# Charging.net
KiCad netlist of a schematic drawn in Altium Designer
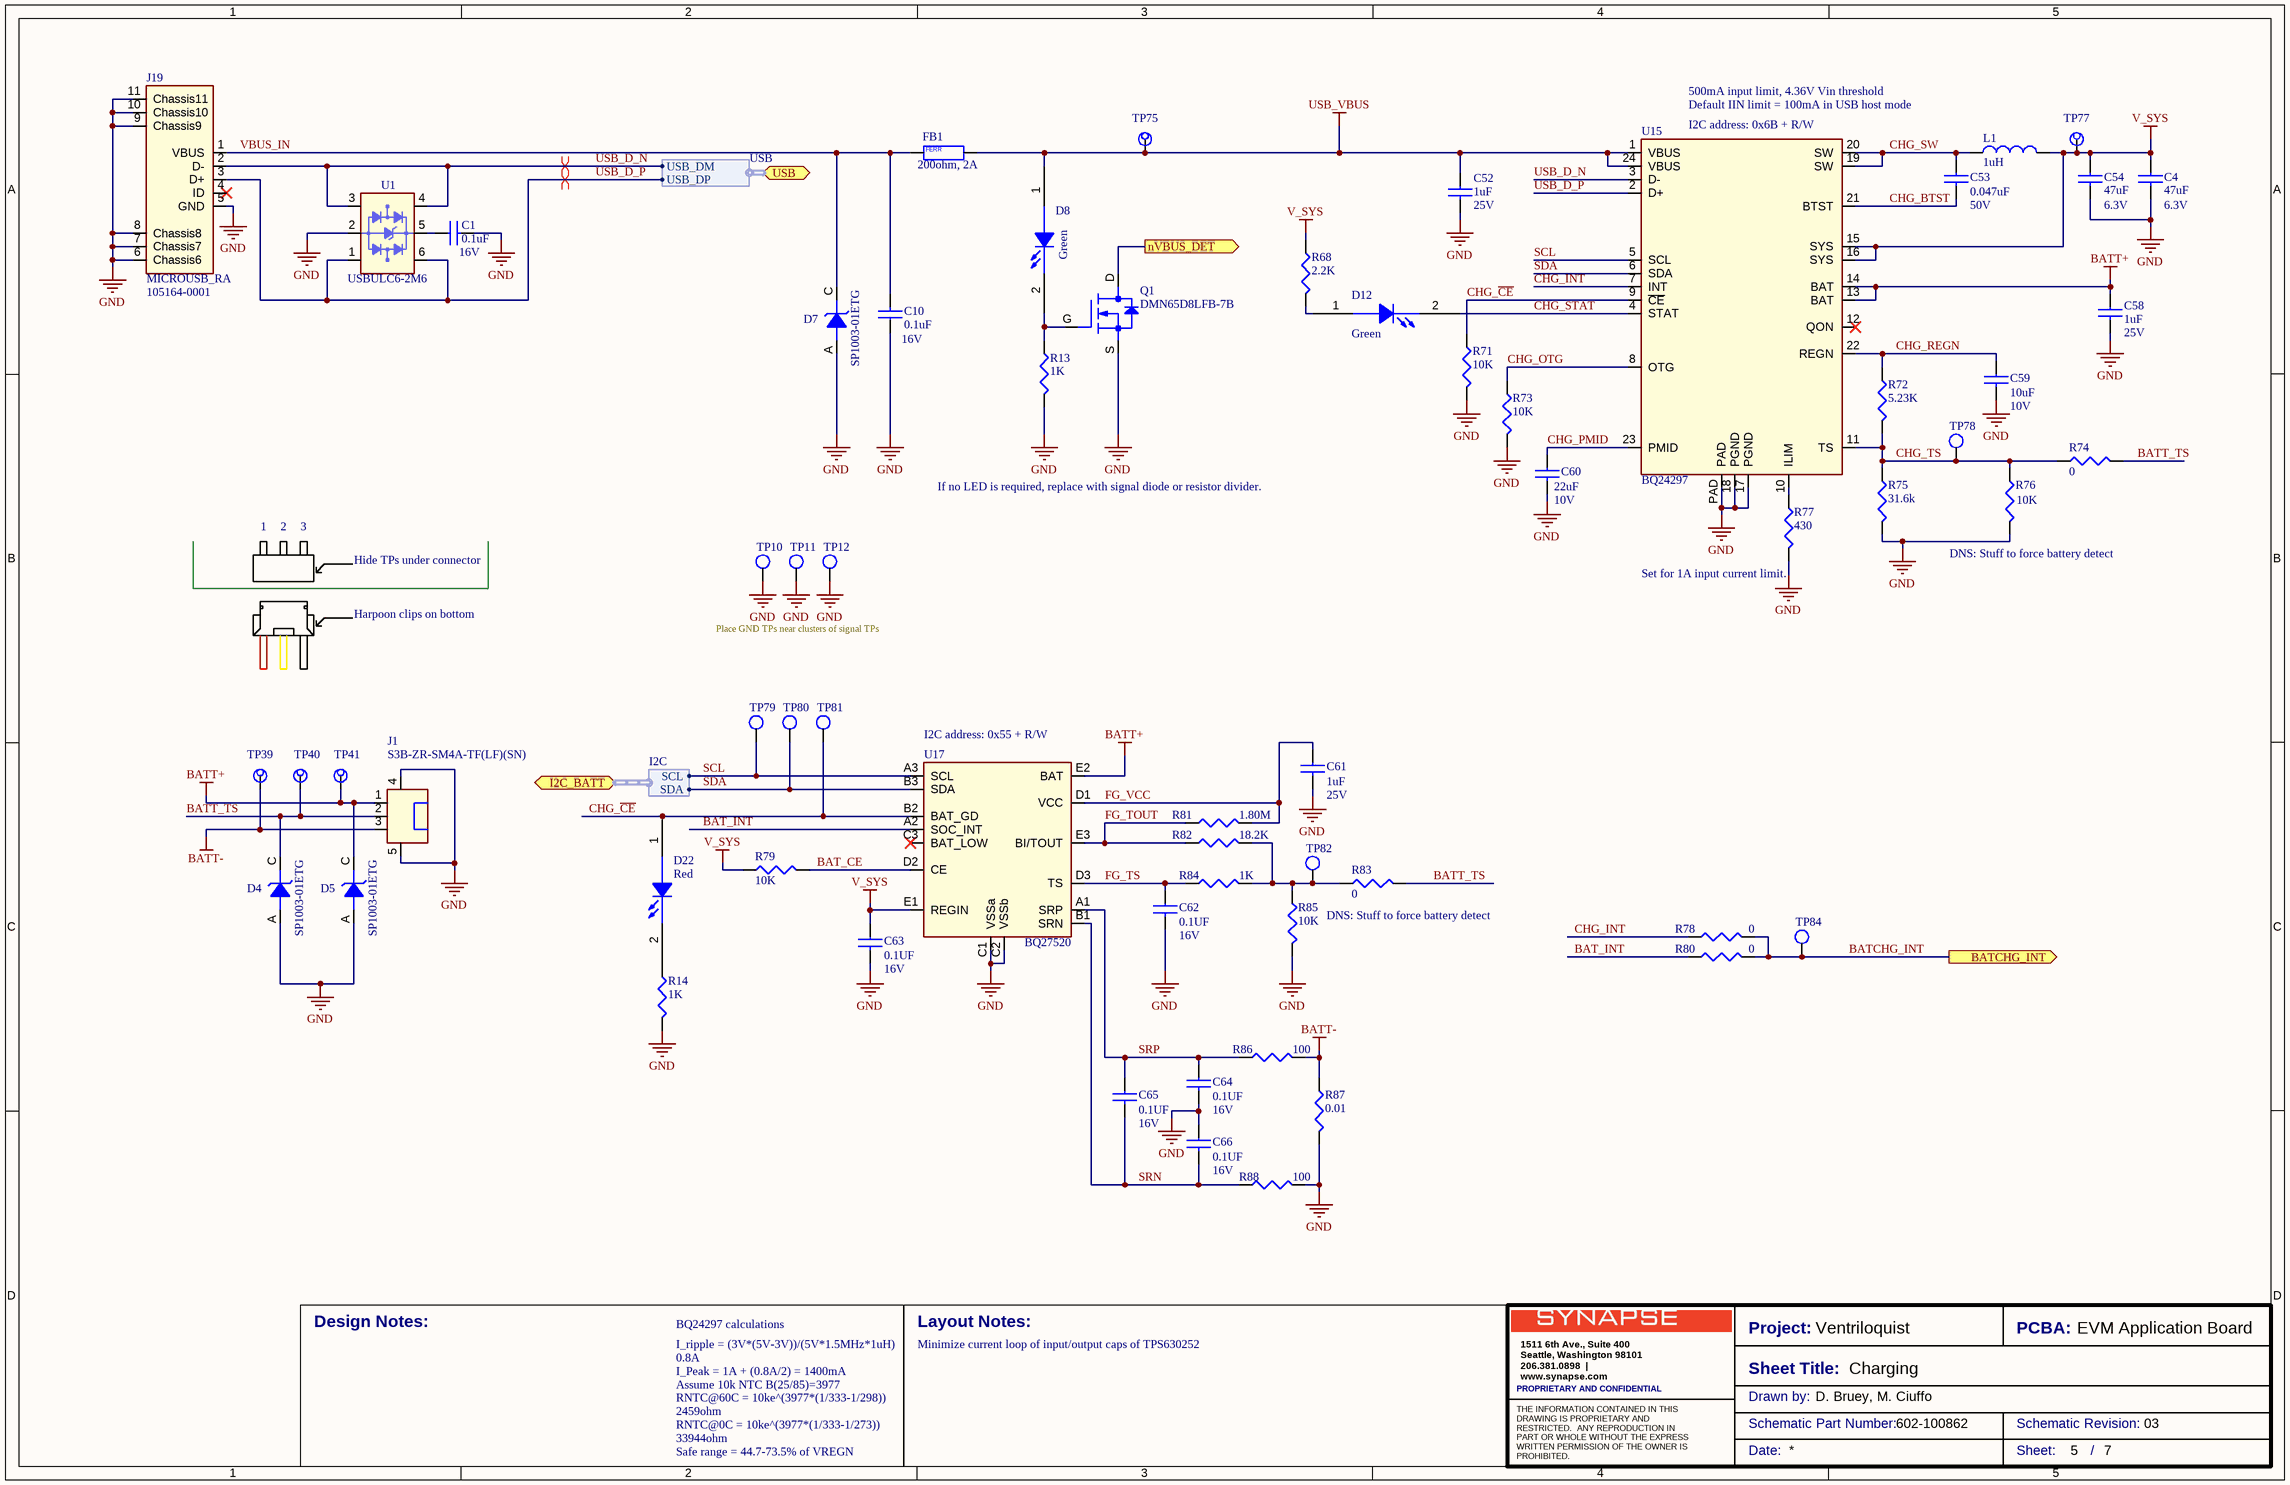
[diagram p0: Charging.SchDoc]

(export (version "E")
  (design (tool "Eeschema 10.0.6"))
  (components
    (comp (ref "C1")
      (value "0.1uF")
      (footprint "0402-IPCsm_55")
      (description "CAP CER .1UF 16V X7R 0402")
      (fields (field (name "VOLTAGE") "16V") (field (name "MFG") "MURATA") (field (name "TOLERANCE") "10%"))
      (libsource (lib "SynapseLibrary") (part "CAP"))
    )
    (comp (ref "C4")
      (value "47uF")
      (footprint "0805-ipcsm_145")
      (description "CAP CER 47UF 6.3V 20% X5R 0805")
      (fields (field (name "VOLTAGE") "6.3V") (field (name "MFG") "TDK") (field (name "TOLERANCE") "20%"))
      (libsource (lib "SynapseLibrary") (part "CAP"))
    )
    (comp (ref "C10")
      (value "0.1uF")
      (footprint "0402-IPCsm_55")
      (description "CAP CER .1UF 16V X7R 0402")
      (fields (field (name "VOLTAGE") "16V") (field (name "MFG") "MURATA") (field (name "TOLERANCE") "10%"))
      (libsource (lib "SynapseLibrary") (part "CAP"))
    )
    (comp (ref "C52")
      (value "1uF")
      (footprint "0603-IPCsm_90")
      (description "CAP CER 1UF 25V 10% X5R 0603")
      (fields (field (name "VOLTAGE") "25V") (field (name "MFG") "Murata") (field (name "TOLERANCE") "10%"))
      (libsource (lib "SynapseLibrary") (part "CAP"))
    )
    (comp (ref "C53")
      (value "0.047uF")
      (footprint "0402-IPCsm_55")
      (description "CAP CER 0.047UF 50V 10% X7R 0402")
      (fields (field (name "VOLTAGE") "50V") (field (name "MFG") "TDK") (field (name "TOLERANCE") "10%"))
      (libsource (lib "SynapseLibrary") (part "CAP"))
    )
    (comp (ref "C54")
      (value "47uF")
      (footprint "0805-ipcsm_145")
      (description "CAP CER 47UF 6.3V 20% X5R 0805")
      (fields (field (name "VOLTAGE") "6.3V") (field (name "MFG") "TDK") (field (name "TOLERANCE") "20%"))
      (libsource (lib "SynapseLibrary") (part "CAP"))
    )
    (comp (ref "C58")
      (value "1uF")
      (footprint "0603-IPCsm_90")
      (description "CAP CER 1UF 25V 10% X5R 0603")
      (fields (field (name "VOLTAGE") "25V") (field (name "MFG") "Murata") (field (name "TOLERANCE") "10%"))
      (libsource (lib "SynapseLibrary") (part "CAP"))
    )
    (comp (ref "C59")
      (value "10uF")
      (footprint "0402-ipcsm_55")
      (description "CAP CER 10UF 10V 20% X5R 0402")
      (fields
        (field (name "VOLTAGE") "10V")
        (field (name "MFG") "Samsung Electro-Mechanics America, Inc")
        (field (name "TOLERANCE") "20%")
      )
      (libsource (lib "SynapseLibrary") (part "CAP"))
    )
    (comp (ref "C60")
      (value "22uF")
      (footprint "0805-IPCsm_100")
      (description "CAP CER 22UF 10V 20% JB 0805")
      (fields (field (name "VOLTAGE") "10V") (field (name "MFG") "TDK") (field (name "TOLERANCE") "20%"))
      (libsource (lib "SynapseLibrary") (part "CAP"))
    )
    (comp (ref "C61")
      (value "1uF")
      (footprint "0603-IPCsm_90")
      (description "CAP CER 1UF 25V 10% X5R 0603")
      (fields (field (name "VOLTAGE") "25V") (field (name "MFG") "Murata") (field (name "TOLERANCE") "10%"))
      (libsource (lib "SynapseLibrary") (part "CAP"))
    )
    (comp (ref "C62")
      (value "0.1UF")
      (footprint "0603-ipcsm_90")
      (description "CAP CER 0.1UF 16V 5% X7R 0603")
      (fields (field (name "VOLTAGE") "16V") (field (name "MFG") "Kemet") (field (name "TOLERANCE") "5%"))
      (libsource (lib "SynapseLibrary") (part "CAP"))
    )
    (comp (ref "C63")
      (value "0.1UF")
      (footprint "0603-ipcsm_90")
      (description "CAP CER 0.1UF 16V 5% X7R 0603")
      (fields (field (name "VOLTAGE") "16V") (field (name "MFG") "Kemet") (field (name "TOLERANCE") "5%"))
      (libsource (lib "SynapseLibrary") (part "CAP"))
    )
    (comp (ref "C64")
      (value "0.1UF")
      (footprint "0603-ipcsm_90")
      (description "CAP CER 0.1UF 16V 5% X7R 0603")
      (fields (field (name "VOLTAGE") "16V") (field (name "MFG") "Kemet") (field (name "TOLERANCE") "5%"))
      (libsource (lib "SynapseLibrary") (part "CAP"))
    )
    (comp (ref "C65")
      (value "0.1UF")
      (footprint "0603-ipcsm_90")
      (description "CAP CER 0.1UF 16V 5% X7R 0603")
      (fields (field (name "VOLTAGE") "16V") (field (name "MFG") "Kemet") (field (name "TOLERANCE") "5%"))
      (libsource (lib "SynapseLibrary") (part "CAP"))
    )
    (comp (ref "C66")
      (value "0.1UF")
      (footprint "0603-ipcsm_90")
      (description "CAP CER 0.1UF 16V 5% X7R 0603")
      (fields (field (name "VOLTAGE") "16V") (field (name "MFG") "Kemet") (field (name "TOLERANCE") "5%"))
      (libsource (lib "SynapseLibrary") (part "CAP"))
    )
    (comp (ref "D4")
      (value "SP1003-01ETG")
      (footprint "SOD882-60")
      (description "TVS DIODE 5VWM 12VC SOD882")
      (fields (field (name "MFG") "Littelfuse Inc."))
      (libsource (lib "SynapseLibrary") (part "TVS_UNI"))
    )
    (comp (ref "D5")
      (value "SP1003-01ETG")
      (footprint "SOD882-60")
      (description "TVS DIODE 5VWM 12VC SOD882")
      (fields (field (name "MFG") "Littelfuse Inc."))
      (libsource (lib "SynapseLibrary") (part "TVS_UNI"))
    )
    (comp (ref "D7")
      (value "SP1003-01ETG")
      (footprint "SOD882-60")
      (description "TVS DIODE 5VWM 12VC SOD882")
      (fields (field (name "MFG") "Littelfuse Inc."))
      (libsource (lib "SynapseLibrary") (part "TVS_UNI"))
    )
    (comp (ref "D8")
      (value "Green")
      (footprint "led_ltst-c191kgkt_s80")
      (description "LED GREEN CLEAR THIN 0603 SMD")
      (fields (field (name "MFG") "Lite-On Inc") (field (name "VOLTAGE") "3.2V"))
      (libsource (lib "SynapseLibrary") (part "LED"))
    )
    (comp (ref "D12")
      (value "Green")
      (footprint "led_ltst-c191kgkt_s80")
      (description "LED GREEN CLEAR THIN 0603 SMD")
      (fields (field (name "MFG") "Lite-On Inc") (field (name "VOLTAGE") "3.2V"))
      (libsource (lib "SynapseLibrary") (part "LED"))
    )
    (comp (ref "D22")
      (value "Red")
      (footprint "LED_LTST-C191KGKT_S80")
      (description "LED RED CLEAR 0603 SMD")
      (fields (field (name "MFG") "Lite-On Inc") (field (name "VOLTAGE") "2V"))
      (libsource (lib "SynapseLibrary") (part "LED"))
    )
    (comp (ref "FB1")
      (value "200ohm, 2A")
      (footprint "ind-0603_38H")
      (description "FERRITE CHIP 220 OHM 2A 0603")
      (fields (field (name "MFG") "TDK Corporation"))
      (libsource (lib "SynapseLibrary") (part "FB_H"))
    )
    (comp (ref "J1")
      (value "S3B-ZR-SM4A-TF(LF)(SN)")
      (footprint "CON_JST_S3B-ZR-SM4A")
      (description "3 Positions Header, Shrouded Connector 0.059\" (1.50mm) Surface Mount, Right Angle Tin")
      (fields (field (name "MFG") "JST Sales America Inc"))
      (libsource (lib "SynapseLibrary") (part "HEADER 3 TABS"))
    )
    (comp (ref "J19")
      (value "MICROUSB_RA")
      (footprint "CON_USB_MOLEX_105164-0001")
      (description "USB - micro B Receptacle Connector 5 Position Surface Mount, Right Angle, Horizontal")
      (fields (field (name "MFG_PN") "105164-0001") (field (name "MFG") "MOLEX"))
      (libsource (lib "SynapseLibrary") (part "USB_MICRO"))
    )
    (comp (ref "L1")
      (value "1uH")
      (footprint "ind-1008_35H")
      (description "INDUCTOR 1.0UH 20% 1600MA 1008")
      (fields (field (name "MFG") "MURATA") (field (name "TOLERANCE") "20%"))
      (libsource (lib "SynapseLibrary") (part "IND_H"))
    )
    (comp (ref "Q1")
      (value "DMN65D8LFB-7B")
      (footprint "DFN3-1006_50H")
      (description "MOSFET N-CH 60V 260MA 3DFN")
      (fields (field (name "MFG") "Diodes") (field (name "VOLTAGE") "60V"))
      (libsource (lib "SynapseLibrary") (part "MOSFET_N_EN_3PIN"))
    )
    (comp (ref "R13")
      (value "1K")
      (footprint "0603-IPCsm_56")
      (description "RES 1K 1/10W 1% 0603 SMD")
      (fields (field (name "TOLERANCE") "1.00%") (field (name "VOLTAGE") "50V"))
      (libsource (lib "SynapseLibrary") (part "RES"))
    )
    (comp (ref "R14")
      (value "1K")
      (footprint "0603-IPCsm_56")
      (description "RES 1K 1/10W 1% 0603 SMD")
      (fields (field (name "TOLERANCE") "1.00%") (field (name "VOLTAGE") "50V"))
      (libsource (lib "SynapseLibrary") (part "RES"))
    )
    (comp (ref "R68")
      (value "2.2K")
      (footprint "0402-IPCsm_40")
      (description "RES SMD 2.2K OHM 5% 1/10W 0402")
      (fields (field (name "TOLERANCE") "5.00%") (field (name "VOLTAGE") "50V"))
      (libsource (lib "SynapseLibrary") (part "RES"))
    )
    (comp (ref "R71")
      (value "10K")
      (footprint "0402-IPCsm_40")
      (description "RES 10K OHM 1/10W 5% 0402 SMD")
      (fields (field (name "TOLERANCE") "5%") (field (name "MFG") "Panasonic"))
      (libsource (lib "SynapseLibrary") (part "RES"))
    )
    (comp (ref "R72")
      (value "5.23K")
      (footprint "0402-IPCsm_40")
      (description "RES 5.23K OHM 1/10W 1% 0402 SMD")
      (fields (field (name "TOLERANCE") "1.00%") (field (name "MFG") "PANASONIC"))
      (libsource (lib "SynapseLibrary") (part "RES"))
    )
    (comp (ref "R73")
      (value "10K")
      (footprint "0402-IPCsm_40")
      (description "RES 10K OHM 1/10W 5% 0402 SMD")
      (fields (field (name "TOLERANCE") "5%") (field (name "MFG") "Panasonic"))
      (libsource (lib "SynapseLibrary") (part "RES"))
    )
    (comp (ref "R74")
      (value "0")
      (footprint "0402-IPCsm_40")
      (description "RES 0.0 OHM 1/10W JUMP 0402 SMD")
      (fields (field (name "TOLERANCE") "5.00%") (field (name "MFG") "PANASONIC"))
      (libsource (lib "SynapseLibrary") (part "RES"))
    )
    (comp (ref "R75")
      (value "31.6k")
      (footprint "0402-IPCsm_40")
      (description "RES 31.6K OHM 0.1W 1% 0402 SMD")
      (fields (field (name "TOLERANCE") "1.00%") (field (name "MFG") "PANASONIC"))
      (libsource (lib "SynapseLibrary") (part "RES"))
    )
    (comp (ref "R76")
      (value "10K")
      (footprint "0402-IPCsm_40")
      (description "RES 10K OHM 1/10W 5% 0402 SMD")
      (fields (field (name "TOLERANCE") "5%") (field (name "MFG") "Panasonic"))
      (libsource (lib "SynapseLibrary") (part "RES"))
    )
    (comp (ref "R77")
      (value "430")
      (footprint "0402-IPCsm_40")
      (description "RES 430 OHM 1/10W 1% 0402 SMD")
      (fields (field (name "TOLERANCE") "1.00%") (field (name "MFG") "PANASONIC"))
      (libsource (lib "SynapseLibrary") (part "RES"))
    )
    (comp (ref "R78")
      (value "0")
      (footprint "0402-IPCsm_40")
      (description "RES 0.0 OHM 1/10W JUMP 0402 SMD")
      (fields (field (name "TOLERANCE") "5.00%") (field (name "MFG") "PANASONIC"))
      (libsource (lib "SynapseLibrary") (part "RES"))
    )
    (comp (ref "R79")
      (value "10K")
      (footprint "0402-IPCsm_40")
      (description "RES 10K OHM 1/10W 5% 0402 SMD")
      (fields (field (name "TOLERANCE") "5%") (field (name "MFG") "Panasonic"))
      (libsource (lib "SynapseLibrary") (part "RES"))
    )
    (comp (ref "R80")
      (value "0")
      (footprint "0402-IPCsm_40")
      (description "RES 0.0 OHM 1/10W JUMP 0402 SMD")
      (fields (field (name "TOLERANCE") "5.00%") (field (name "MFG") "PANASONIC"))
      (libsource (lib "SynapseLibrary") (part "RES"))
    )
    (comp (ref "R81")
      (value "1.80M")
      (footprint "0603-IPCsm_56")
      (description "RES 1.80M OHM 1/10W 1% 0603 SMD")
      (fields (field (name "TOLERANCE") "1.00%") (field (name "MFG") "PANASONIC"))
      (libsource (lib "SynapseLibrary") (part "RES"))
    )
    (comp (ref "R82")
      (value "18.2K")
      (footprint "0603-IPCsm_56")
      (description "RES 18.2K OHM 1/10W 1% 0603 SMD")
      (fields (field (name "TOLERANCE") "1.00%") (field (name "MFG") "PANASONIC"))
      (libsource (lib "SynapseLibrary") (part "RES"))
    )
    (comp (ref "R83")
      (value "0")
      (footprint "0402-IPCsm_40")
      (description "RES 0.0 OHM 1/10W JUMP 0402 SMD")
      (fields (field (name "TOLERANCE") "5.00%") (field (name "MFG") "PANASONIC"))
      (libsource (lib "SynapseLibrary") (part "RES"))
    )
    (comp (ref "R84")
      (value "1K")
      (footprint "0603-IPCsm_56")
      (description "RES 1K 1/10W 1% 0603 SMD")
      (fields (field (name "TOLERANCE") "1.00%") (field (name "VOLTAGE") "50V"))
      (libsource (lib "SynapseLibrary") (part "RES"))
    )
    (comp (ref "R85")
      (value "10K")
      (footprint "0402-IPCsm_40")
      (description "RES 10K OHM 1/10W 5% 0402 SMD")
      (fields (field (name "TOLERANCE") "5%") (field (name "MFG") "Panasonic"))
      (libsource (lib "SynapseLibrary") (part "RES"))
    )
    (comp (ref "R86")
      (value "100")
      (footprint "0603-IPCsm_56")
      (description "RES 100 OHM 1/10W 5% 0603 SMD")
      (fields (field (name "TOLERANCE") "5.00%") (field (name "MFG") "PANASONIC"))
      (libsource (lib "SynapseLibrary") (part "RES"))
    )
    (comp (ref "R87")
      (value "0.01")
      (footprint "r-0805_20H")
      (description "RES 0.01 OHM 1/2W 1% 0805 SMD")
      (fields (field (name "TOLERANCE") "1%") (field (name "MFG") "Rohm Semiconductor"))
      (libsource (lib "SynapseLibrary") (part "RES"))
    )
    (comp (ref "R88")
      (value "100")
      (footprint "0603-IPCsm_56")
      (description "RES 100 OHM 1/10W 5% 0603 SMD")
      (fields (field (name "TOLERANCE") "5.00%") (field (name "MFG") "PANASONIC"))
      (libsource (lib "SynapseLibrary") (part "RES"))
    )
    (comp (ref "TP10")
      (value "tp-1mm")
      (footprint "TP-S100_SMT")
      (description "TESTPOINT, 1MM SMD, Square pad, Round SM opening")
      (fields (field (name "MFG") "NA"))
      (libsource (lib "SynapseLibrary") (part "tp_smt"))
    )
    (comp (ref "TP11")
      (value "tp-1mm")
      (footprint "TP-S100_SMT")
      (description "TESTPOINT, 1MM SMD, Square pad, Round SM opening")
      (fields (field (name "MFG") "NA"))
      (libsource (lib "SynapseLibrary") (part "tp_smt"))
    )
    (comp (ref "TP12")
      (value "tp-1mm")
      (footprint "TP-S100_SMT")
      (description "TESTPOINT, 1MM SMD, Square pad, Round SM opening")
      (fields (field (name "MFG") "NA"))
      (libsource (lib "SynapseLibrary") (part "tp_smt"))
    )
    (comp (ref "TP39")
      (value "TPC150H080P")
      (footprint "TPC150H080P")
      (description "TESTPOINT, 1.5mm pad, 0.8 mm plated")
      (fields (field (name "MFG") "NA"))
      (libsource (lib "SynapseLibrary") (part "tp_th"))
    )
    (comp (ref "TP40")
      (value "TPC150H080P")
      (footprint "TPC150H080P")
      (description "TESTPOINT, 1.5mm pad, 0.8 mm plated")
      (fields (field (name "MFG") "NA"))
      (libsource (lib "SynapseLibrary") (part "tp_th"))
    )
    (comp (ref "TP41")
      (value "TPC150H080P")
      (footprint "TPC150H080P")
      (description "TESTPOINT, 1.5mm pad, 0.8 mm plated")
      (fields (field (name "MFG") "NA"))
      (libsource (lib "SynapseLibrary") (part "tp_th"))
    )
    (comp (ref "TP75")
      (value "TPC150H080P")
      (footprint "TPC150H080P")
      (description "TESTPOINT, 1.5mm pad, 0.8 mm plated")
      (fields (field (name "MFG") "NA"))
      (libsource (lib "SynapseLibrary") (part "tp_th"))
    )
    (comp (ref "TP77")
      (value "TPC150H080P")
      (footprint "TPC150H080P")
      (description "TESTPOINT, 1.5mm pad, 0.8 mm plated")
      (fields (field (name "MFG") "NA"))
      (libsource (lib "SynapseLibrary") (part "tp_th"))
    )
    (comp (ref "TP78")
      (value "tp-1mm")
      (footprint "TP-S100_SMT")
      (description "TESTPOINT, 1MM SMD, Square pad, Round SM opening")
      (fields (field (name "MFG") "NA"))
      (libsource (lib "SynapseLibrary") (part "tp_smt"))
    )
    (comp (ref "TP79")
      (value "tp-1mm")
      (footprint "TP-S100_SMT")
      (description "TESTPOINT, 1MM SMD, Square pad, Round SM opening")
      (fields (field (name "MFG") "NA"))
      (libsource (lib "SynapseLibrary") (part "tp_smt"))
    )
    (comp (ref "TP80")
      (value "tp-1mm")
      (footprint "TP-S100_SMT")
      (description "TESTPOINT, 1MM SMD, Square pad, Round SM opening")
      (fields (field (name "MFG") "NA"))
      (libsource (lib "SynapseLibrary") (part "tp_smt"))
    )
    (comp (ref "TP81")
      (value "tp-1mm")
      (footprint "TP-S100_SMT")
      (description "TESTPOINT, 1MM SMD, Square pad, Round SM opening")
      (fields (field (name "MFG") "NA"))
      (libsource (lib "SynapseLibrary") (part "tp_smt"))
    )
    (comp (ref "TP82")
      (value "tp-1mm")
      (footprint "TP-S100_SMT")
      (description "TESTPOINT, 1MM SMD, Square pad, Round SM opening")
      (fields (field (name "MFG") "NA"))
      (libsource (lib "SynapseLibrary") (part "tp_smt"))
    )
    (comp (ref "TP84")
      (value "tp-1mm")
      (footprint "TP-S100_SMT")
      (description "TESTPOINT, 1MM SMD, Square pad, Round SM opening")
      (fields (field (name "MFG") "NA"))
      (libsource (lib "SynapseLibrary") (part "tp_smt"))
    )
    (comp (ref "U1")
      (value "USBULC6-2M6")
      (footprint "UQFN6_ USBULC6-2M6")
      (description "TVS DIODE 5VWM 17VC 6VFQFPN")
      (fields (field (name "MFG") "ST"))
      (libsource (lib "SynapseLibrary") (part "USBULC6-2M6"))
    )
    (comp (ref "U15")
      (value "BQ24297")
      (footprint "QFN24_BQ24297RGE")
      (description "IC LI+ CHARGER PWR MGMT 24VQFN")
      (fields (field (name "MFG") "TI"))
      (libsource (lib "SynapseLibrary") (part "BQ24297"))
    )
    (comp (ref "U17")
      (value "BQ27520")
      (footprint "BGA15_BQ27520YZFR")
      (description "IC BATT FUEL GAUGE LIION 15DSBGA")
      (fields (field (name "MFG") "TI"))
      (libsource (lib "SynapseLibrary") (part "BQ27520"))
    )
  )
  (nets
    (net (code "3") (name "/BATCHG_INT") (class "Default")
      (node (ref "R78") (pin "2") (pinfunction "2_2") (pintype "passive"))
      (node (ref "R80") (pin "2") (pinfunction "2_2") (pintype "passive"))
      (node (ref "TP84") (pin "1") (pinfunction "TP_1") (pintype "passive"))
    )
    (net (code "4") (name "/BATT_TS") (class "Default")
      (node (ref "D4") (pin "C") (pinfunction "C_C") (pintype "passive"))
      (node (ref "J1") (pin "2") (pinfunction "2_2") (pintype "passive"))
      (node (ref "R74") (pin "2") (pinfunction "2_2") (pintype "passive"))
      (node (ref "R83") (pin "2") (pinfunction "2_2") (pintype "passive"))
      (node (ref "TP40") (pin "1") (pinfunction "TP_1") (pintype "passive"))
    )
    (net (code "5") (name "/BAT_CE") (class "Default")
      (node (ref "R79") (pin "2") (pinfunction "2_2") (pintype "passive"))
      (node (ref "U17") (pin "D2") (pinfunction "CE_D2") (pintype "passive"))
    )
    (net (code "6") (name "/BAT_INT") (class "Default")
      (node (ref "R80") (pin "1") (pinfunction "1_1") (pintype "passive"))
      (node (ref "U17") (pin "A2") (pinfunction "SOC_INT_A2") (pintype "passive"))
    )
    (net (code "7") (name "/CHG_BTST") (class "Default")
      (node (ref "C53") (pin "2") (pinfunction "2_2") (pintype "passive"))
      (node (ref "U15") (pin "21") (pinfunction "BTST_21") (pintype "passive"))
    )
    (net (code "8") (name "/CHG_INT") (class "Default")
      (node (ref "R78") (pin "1") (pinfunction "1_1") (pintype "passive"))
      (node (ref "U15") (pin "7") (pinfunction "INT_7") (pintype "passive"))
    )
    (net (code "9") (name "/CHG_OTG") (class "Default")
      (node (ref "R73") (pin "1") (pinfunction "1_1") (pintype "passive"))
      (node (ref "U15") (pin "8") (pinfunction "OTG_8") (pintype "passive"))
    )
    (net (code "10") (name "/CHG_PMID") (class "Default")
      (node (ref "C60") (pin "1") (pinfunction "1_1") (pintype "passive"))
      (node (ref "U15") (pin "23") (pinfunction "PMID_23") (pintype "passive"))
    )
    (net (code "11") (name "/CHG_REGN") (class "Default")
      (node (ref "C59") (pin "1") (pinfunction "1_1") (pintype "passive"))
      (node (ref "R72") (pin "1") (pinfunction "1_1") (pintype "passive"))
      (node (ref "U15") (pin "22") (pinfunction "REGN_22") (pintype "passive"))
    )
    (net (code "12") (name "/CHG_STAT") (class "Default")
      (node (ref "D12") (pin "2") (pinfunction "C_2") (pintype "passive"))
      (node (ref "U15") (pin "4") (pinfunction "STAT_4") (pintype "passive"))
    )
    (net (code "13") (name "/CHG_SW") (class "Default")
      (node (ref "C53") (pin "1") (pinfunction "1_1") (pintype "passive"))
      (node (ref "L1") (pin "1") (pinfunction "1_1") (pintype "passive"))
      (node (ref "U15") (pin "19") (pinfunction "SW_19") (pintype "passive"))
      (node (ref "U15") (pin "20") (pinfunction "SW_20") (pintype "passive"))
    )
    (net (code "14") (name "/CHG_TS") (class "Default")
      (node (ref "R72") (pin "2") (pinfunction "2_2") (pintype "passive"))
      (node (ref "R74") (pin "1") (pinfunction "1_1") (pintype "passive"))
      (node (ref "R75") (pin "1") (pinfunction "1_1") (pintype "passive"))
      (node (ref "R76") (pin "1") (pinfunction "1_1") (pintype "passive"))
      (node (ref "TP78") (pin "1") (pinfunction "TP_1") (pintype "passive"))
      (node (ref "U15") (pin "11") (pinfunction "TS_11") (pintype "passive"))
    )
    (net (code "15") (name "/CHG_~{CE}") (class "Default")
      (node (ref "D22") (pin "1") (pinfunction "A_1") (pintype "passive"))
      (node (ref "R71") (pin "1") (pinfunction "1_1") (pintype "passive"))
      (node (ref "TP81") (pin "1") (pinfunction "TP_1") (pintype "passive"))
      (node (ref "U15") (pin "9") (pinfunction "~{CE}_9") (pintype "passive"))
      (node (ref "U17") (pin "B2") (pinfunction "BAT_GD_B2") (pintype "passive"))
    )
    (net (code "16") (name "/FG_TOUT") (class "Default")
      (node (ref "R81") (pin "2") (pinfunction "2_2") (pintype "passive"))
      (node (ref "R82") (pin "2") (pinfunction "2_2") (pintype "passive"))
      (node (ref "U17") (pin "E3") (pinfunction "BI/TOUT_E3") (pintype "passive"))
    )
    (net (code "17") (name "/FG_TS") (class "Default")
      (node (ref "C62") (pin "1") (pinfunction "1_1") (pintype "passive"))
      (node (ref "R84") (pin "1") (pinfunction "1_1") (pintype "passive"))
      (node (ref "U17") (pin "D3") (pinfunction "TS_D3") (pintype "passive"))
    )
    (net (code "18") (name "/FG_VCC") (class "Default")
      (node (ref "C61") (pin "1") (pinfunction "1_1") (pintype "passive"))
      (node (ref "R81") (pin "1") (pinfunction "1_1") (pintype "passive"))
      (node (ref "U17") (pin "D1") (pinfunction "VCC_D1") (pintype "passive"))
    )
    (net (code "19") (name "/SCL") (class "Default")
      (node (ref "TP79") (pin "1") (pinfunction "TP_1") (pintype "passive"))
      (node (ref "U15") (pin "5") (pinfunction "SCL_5") (pintype "passive"))
      (node (ref "U17") (pin "A3") (pinfunction "SCL_A3") (pintype "passive"))
    )
    (net (code "20") (name "/SDA") (class "Default")
      (node (ref "TP80") (pin "1") (pinfunction "TP_1") (pintype "passive"))
      (node (ref "U15") (pin "6") (pinfunction "SDA_6") (pintype "passive"))
      (node (ref "U17") (pin "B3") (pinfunction "SDA_B3") (pintype "passive"))
    )
    (net (code "21") (name "/SRN") (class "Default")
      (node (ref "C65") (pin "2") (pinfunction "2_2") (pintype "passive"))
      (node (ref "C66") (pin "2") (pinfunction "2_2") (pintype "passive"))
      (node (ref "R88") (pin "1") (pinfunction "1_1") (pintype "passive"))
      (node (ref "U17") (pin "B1") (pinfunction "SRN_B1") (pintype "passive"))
    )
    (net (code "22") (name "/SRP") (class "Default")
      (node (ref "C64") (pin "1") (pinfunction "1_1") (pintype "passive"))
      (node (ref "C65") (pin "1") (pinfunction "1_1") (pintype "passive"))
      (node (ref "R86") (pin "1") (pinfunction "1_1") (pintype "passive"))
      (node (ref "U17") (pin "A1") (pinfunction "SRP_A1") (pintype "passive"))
    )
    (net (code "23") (name "/USB_D_N") (class "Default")
      (node (ref "J19") (pin "2") (pinfunction "D-_2") (pintype "passive"))
      (node (ref "U1") (pin "3") (pinfunction "I/O2_3") (pintype "passive"))
      (node (ref "U1") (pin "4") (pinfunction "I/O3_4") (pintype "passive"))
      (node (ref "U15") (pin "3") (pinfunction "D-_3") (pintype "passive"))
    )
    (net (code "24") (name "/USB_D_P") (class "Default")
      (node (ref "J19") (pin "3") (pinfunction "D+_3") (pintype "passive"))
      (node (ref "U1") (pin "1") (pinfunction "I/O1_1") (pintype "passive"))
      (node (ref "U1") (pin "6") (pinfunction "I/O4_6") (pintype "passive"))
      (node (ref "U15") (pin "2") (pinfunction "D+_2") (pintype "passive"))
    )
    (net (code "25") (name "/VBUS_IN") (class "Default")
      (node (ref "C10") (pin "2") (pinfunction "2_2") (pintype "passive"))
      (node (ref "D7") (pin "C") (pinfunction "C_C") (pintype "passive"))
      (node (ref "FB1") (pin "2") (pinfunction "ENDB_2") (pintype "passive"))
      (node (ref "J19") (pin "1") (pinfunction "VBUS_1") (pintype "power_in"))
    )
    (net (code "26") (name "/nVBUS_DET") (class "Default")
      (node (ref "Q1") (pin "D") (pinfunction "D_D") (pintype "passive"))
    )
    (net (code "29") (name "BATT+") (class "Default")
      (node (ref "C58") (pin "1") (pinfunction "1_1") (pintype "passive"))
      (node (ref "D5") (pin "C") (pinfunction "C_C") (pintype "passive"))
      (node (ref "J1") (pin "1") (pinfunction "1_1") (pintype "passive"))
      (node (ref "TP41") (pin "1") (pinfunction "TP_1") (pintype "passive"))
      (node (ref "U15") (pin "13") (pinfunction "BAT_13") (pintype "passive"))
      (node (ref "U15") (pin "14") (pinfunction "BAT_14") (pintype "passive"))
      (node (ref "U17") (pin "E2") (pinfunction "BAT_E2") (pintype "passive"))
    )
    (net (code "30") (name "BATT-") (class "Default")
      (node (ref "J1") (pin "3") (pinfunction "3_3") (pintype "passive"))
      (node (ref "R86") (pin "2") (pinfunction "2_2") (pintype "passive"))
      (node (ref "R87") (pin "1") (pinfunction "1_1") (pintype "passive"))
      (node (ref "TP39") (pin "1") (pinfunction "TP_1") (pintype "passive"))
    )
    (net (code "31") (name "GND") (class "Default")
      (node (ref "C1") (pin "2") (pinfunction "2_2") (pintype "passive"))
      (node (ref "C10") (pin "1") (pinfunction "1_1") (pintype "passive"))
      (node (ref "C4") (pin "2") (pinfunction "2_2") (pintype "passive"))
      (node (ref "C52") (pin "2") (pinfunction "2_2") (pintype "passive"))
      (node (ref "C54") (pin "2") (pinfunction "2_2") (pintype "passive"))
      (node (ref "C58") (pin "2") (pinfunction "2_2") (pintype "passive"))
      (node (ref "C59") (pin "2") (pinfunction "2_2") (pintype "passive"))
      (node (ref "C60") (pin "2") (pinfunction "2_2") (pintype "passive"))
      (node (ref "C61") (pin "2") (pinfunction "2_2") (pintype "passive"))
      (node (ref "C62") (pin "2") (pinfunction "2_2") (pintype "passive"))
      (node (ref "C63") (pin "2") (pinfunction "2_2") (pintype "passive"))
      (node (ref "C64") (pin "2") (pinfunction "2_2") (pintype "passive"))
      (node (ref "C66") (pin "1") (pinfunction "1_1") (pintype "passive"))
      (node (ref "D4") (pin "A") (pinfunction "A_A") (pintype "passive"))
      (node (ref "D5") (pin "A") (pinfunction "A_A") (pintype "passive"))
      (node (ref "D7") (pin "A") (pinfunction "A_A") (pintype "passive"))
      (node (ref "J1") (pin "4") (pinfunction "TAB1_4") (pintype "passive"))
      (node (ref "J1") (pin "5") (pinfunction "TAB2_5") (pintype "passive"))
      (node (ref "J19") (pin "10") (pinfunction "Chassis10_10") (pintype "passive"))
      (node (ref "J19") (pin "11") (pinfunction "Chassis11_11") (pintype "passive"))
      (node (ref "J19") (pin "5") (pinfunction "GND_5") (pintype "power_in"))
      (node (ref "J19") (pin "6") (pinfunction "Chassis6_6") (pintype "passive"))
      (node (ref "J19") (pin "7") (pinfunction "Chassis7_7") (pintype "passive"))
      (node (ref "J19") (pin "8") (pinfunction "Chassis8_8") (pintype "passive"))
      (node (ref "J19") (pin "9") (pinfunction "Chassis9_9") (pintype "passive"))
      (node (ref "Q1") (pin "S") (pinfunction "S_S") (pintype "passive"))
      (node (ref "R13") (pin "2") (pinfunction "2_2") (pintype "passive"))
      (node (ref "R14") (pin "2") (pinfunction "2_2") (pintype "passive"))
      (node (ref "R71") (pin "2") (pinfunction "2_2") (pintype "passive"))
      (node (ref "R73") (pin "2") (pinfunction "2_2") (pintype "passive"))
      (node (ref "R75") (pin "2") (pinfunction "2_2") (pintype "passive"))
      (node (ref "R76") (pin "2") (pinfunction "2_2") (pintype "passive"))
      (node (ref "R77") (pin "2") (pinfunction "2_2") (pintype "passive"))
      (node (ref "R85") (pin "2") (pinfunction "2_2") (pintype "passive"))
      (node (ref "R87") (pin "2") (pinfunction "2_2") (pintype "passive"))
      (node (ref "R88") (pin "2") (pinfunction "2_2") (pintype "passive"))
      (node (ref "TP10") (pin "1") (pinfunction "TP_1") (pintype "passive"))
      (node (ref "TP11") (pin "1") (pinfunction "TP_1") (pintype "passive"))
      (node (ref "TP12") (pin "1") (pinfunction "TP_1") (pintype "passive"))
      (node (ref "U1") (pin "2") (pinfunction "GND_2") (pintype "passive"))
      (node (ref "U15") (pin "17") (pinfunction "PGND_17") (pintype "passive"))
      (node (ref "U15") (pin "18") (pinfunction "PGND_18") (pintype "passive"))
      (node (ref "U15") (pin "PAD") (pinfunction "PAD_PAD") (pintype "passive"))
      (node (ref "U17") (pin "C1") (pinfunction "VSSa_C1") (pintype "passive"))
      (node (ref "U17") (pin "C2") (pinfunction "VSSb_C2") (pintype "passive"))
    )
    (net (code "32") (name "Net-(D8-C)") (class "Default")
      (node (ref "D8") (pin "2") (pinfunction "C_2") (pintype "passive"))
      (node (ref "Q1") (pin "G") (pinfunction "G_G") (pintype "passive"))
      (node (ref "R13") (pin "1") (pinfunction "1_1") (pintype "passive"))
    )
    (net (code "33") (name "Net-(D12-A)") (class "Default")
      (node (ref "D12") (pin "1") (pinfunction "A_1") (pintype "passive"))
      (node (ref "R68") (pin "2") (pinfunction "2_2") (pintype "passive"))
    )
    (net (code "34") (name "Net-(D22-C)") (class "Default")
      (node (ref "D22") (pin "2") (pinfunction "C_2") (pintype "passive"))
      (node (ref "R14") (pin "1") (pinfunction "1_1") (pintype "passive"))
    )
    (net (code "35") (name "Net-(TP82-TP)") (class "Default")
      (node (ref "R82") (pin "1") (pinfunction "1_1") (pintype "passive"))
      (node (ref "R83") (pin "1") (pinfunction "1_1") (pintype "passive"))
      (node (ref "R84") (pin "2") (pinfunction "2_2") (pintype "passive"))
      (node (ref "R85") (pin "1") (pinfunction "1_1") (pintype "passive"))
      (node (ref "TP82") (pin "1") (pinfunction "TP_1") (pintype "passive"))
    )
    (net (code "36") (name "Net-(U1-VDD)") (class "Default")
      (node (ref "C1") (pin "1") (pinfunction "1_1") (pintype "passive"))
      (node (ref "U1") (pin "5") (pinfunction "VDD_5") (pintype "passive"))
    )
    (net (code "37") (name "Net-(U15-ILIM)") (class "Default")
      (node (ref "R77") (pin "1") (pinfunction "1_1") (pintype "passive"))
      (node (ref "U15") (pin "10") (pinfunction "ILIM_10") (pintype "passive"))
    )
    (net (code "38") (name "USB_VBUS") (class "Default")
      (node (ref "C52") (pin "1") (pinfunction "1_1") (pintype "passive"))
      (node (ref "D8") (pin "1") (pinfunction "A_1") (pintype "passive"))
      (node (ref "FB1") (pin "1") (pinfunction "ENDA_1") (pintype "passive"))
      (node (ref "TP75") (pin "1") (pinfunction "TP_1") (pintype "passive"))
      (node (ref "U15") (pin "1") (pinfunction "VBUS_1") (pintype "passive"))
      (node (ref "U15") (pin "24") (pinfunction "VBUS_24") (pintype "passive"))
    )
    (net (code "39") (name "V_SYS") (class "Default")
      (node (ref "C4") (pin "1") (pinfunction "1_1") (pintype "passive"))
      (node (ref "C54") (pin "1") (pinfunction "1_1") (pintype "passive"))
      (node (ref "C63") (pin "1") (pinfunction "1_1") (pintype "passive"))
      (node (ref "L1") (pin "2") (pinfunction "2_2") (pintype "passive"))
      (node (ref "R68") (pin "1") (pinfunction "1_1") (pintype "passive"))
      (node (ref "R79") (pin "1") (pinfunction "1_1") (pintype "passive"))
      (node (ref "TP77") (pin "1") (pinfunction "TP_1") (pintype "passive"))
      (node (ref "U15") (pin "15") (pinfunction "SYS_15") (pintype "passive"))
      (node (ref "U15") (pin "16") (pinfunction "SYS_16") (pintype "passive"))
      (node (ref "U17") (pin "E1") (pinfunction "REGIN_E1") (pintype "passive"))
    )
    (net (code "40") (name "unconnected-(J19-ID-Pad4)") (class "Default")
      (node (ref "J19") (pin "4") (pinfunction "ID_4") (pintype "passive+no_connect"))
    )
    (net (code "41") (name "unconnected-(U15-QON-Pad12)") (class "Default")
      (node (ref "U15") (pin "12") (pinfunction "QON_12") (pintype "passive+no_connect"))
    )
    (net (code "42") (name "unconnected-(U17-BAT_LOW-PadC3)") (class "Default")
      (node (ref "U17") (pin "C3") (pinfunction "BAT_LOW_C3") (pintype "passive+no_connect"))
    )
  )
)
